# penvmon.net
KiCad netlist of a schematic drawn in EAGLE
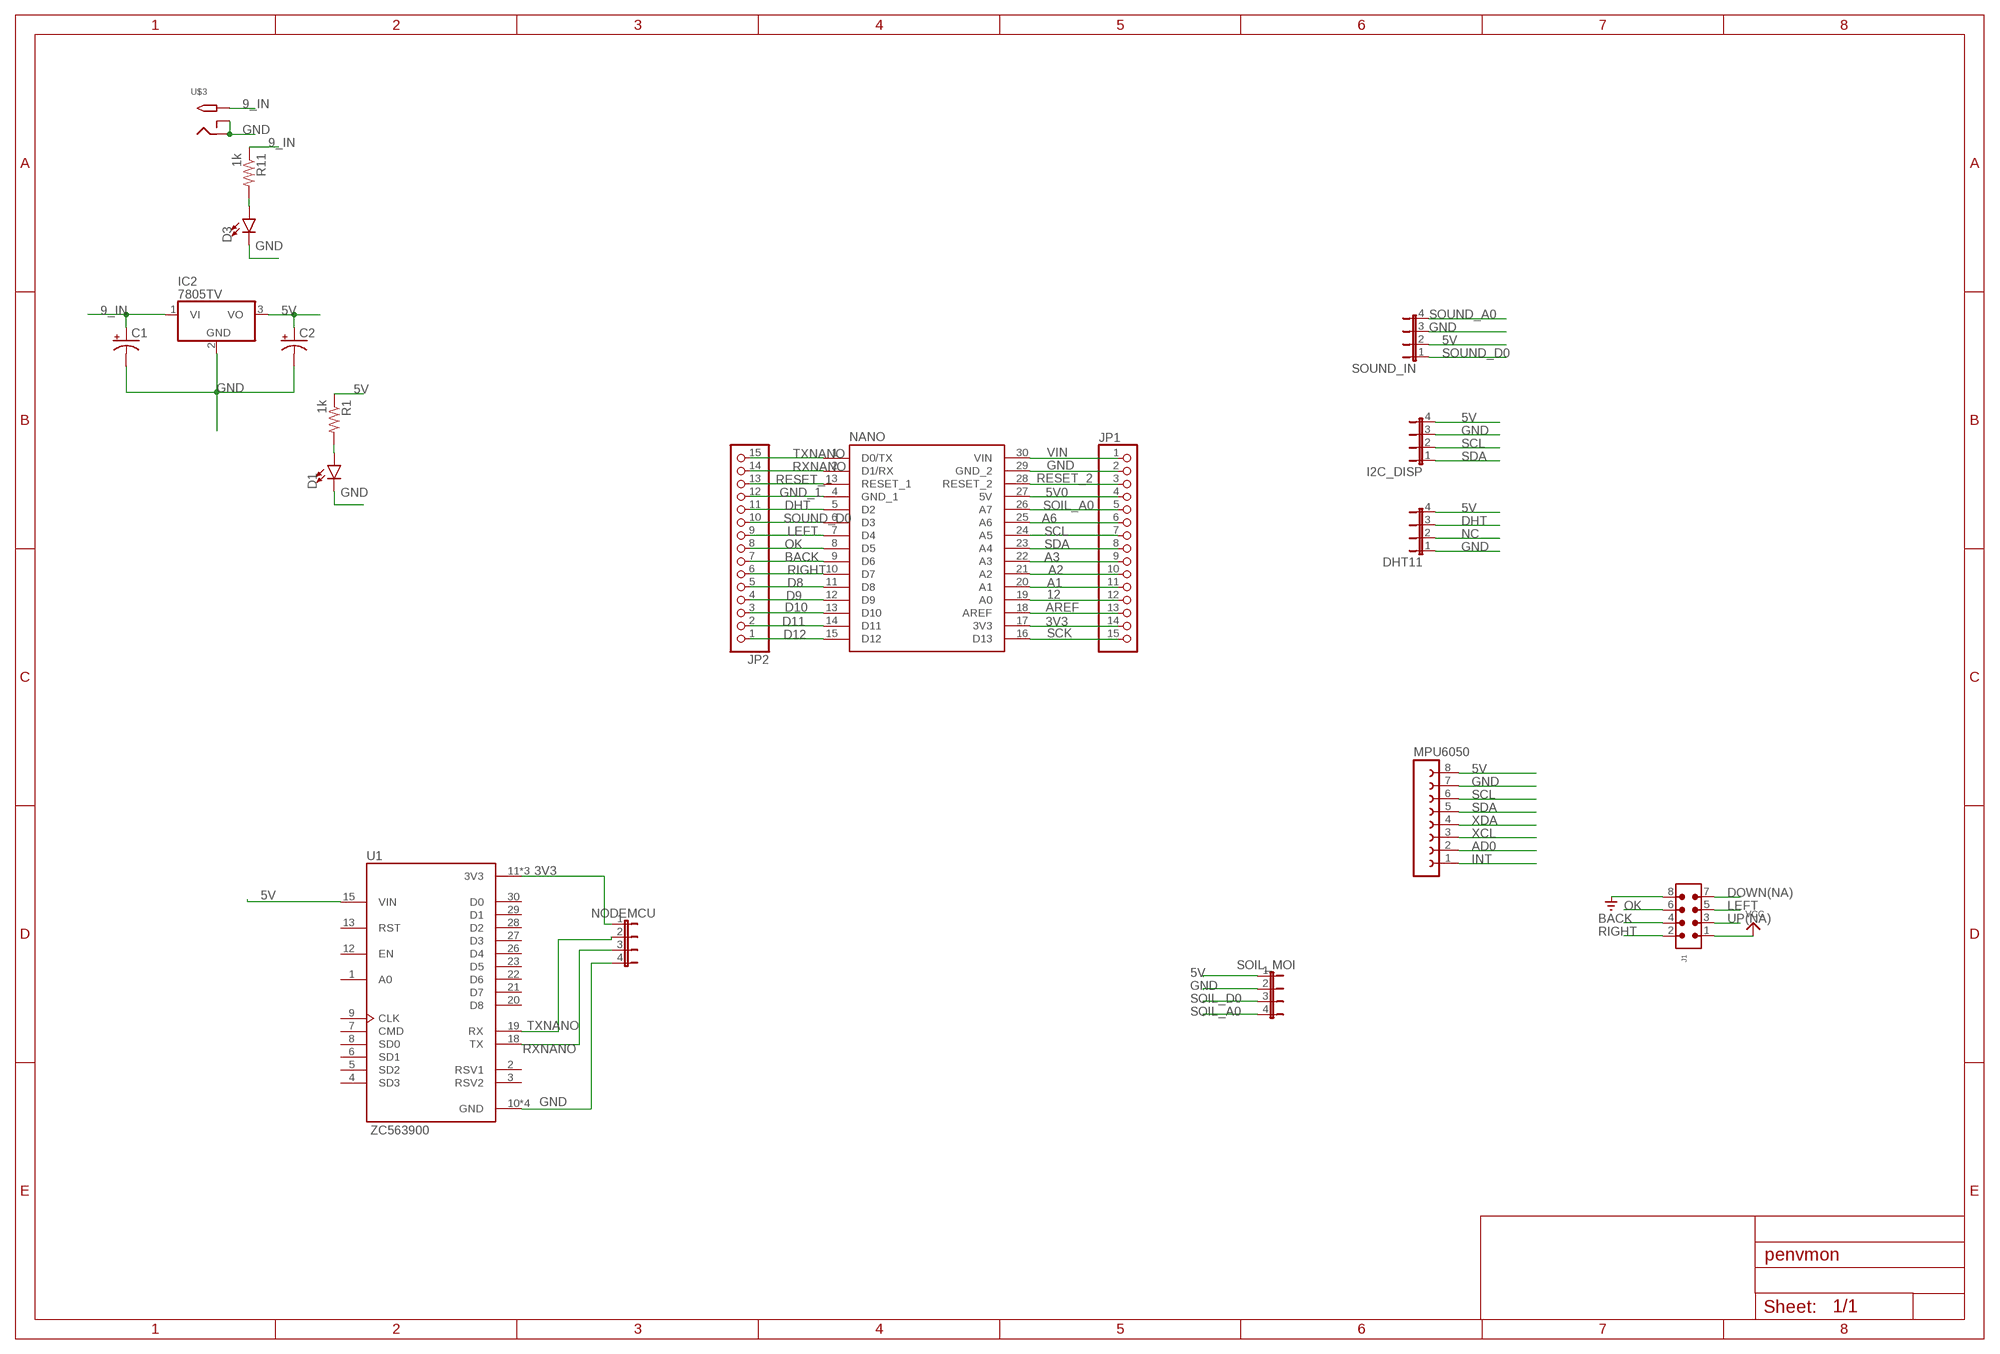
[diagram p0: schematic, sheet 1]

(export (version "E")
  (design (tool "Eeschema 10.0.6"))
  (components
    (comp (ref "C1")
      (value "CPOL-USE3.5-8")
      (footprint "eagle-import:E3,5-8")
      (libsource (lib "eagle-import") (part "CPOL-USE3.5-8"))
    )
    (comp (ref "C2")
      (value "CPOL-USE3.5-8")
      (footprint "eagle-import:E3,5-8")
      (libsource (lib "eagle-import") (part "CPOL-USE3.5-8"))
    )
    (comp (ref "D1")
      (value "LED3MM")
      (footprint "eagle-import:LED_3MM")
      (libsource (lib "eagle-import") (part "LED3MM"))
    )
    (comp (ref "D3")
      (value "LED3MM")
      (footprint "eagle-import:LED_3MM")
      (libsource (lib "eagle-import") (part "LED3MM"))
    )
    (comp (ref "DHT11")
      (value "JP4E")
      (footprint "eagle-import:JP4")
      (libsource (lib "eagle-import") (part "JP4E"))
    )
    (comp (ref "I2C_DISP")
      (value "JP4E")
      (footprint "eagle-import:JP4")
      (libsource (lib "eagle-import") (part "JP4E"))
    )
    (comp (ref "IC2")
      (value "7805TV")
      (footprint "eagle-import:TO220V")
      (libsource (lib "eagle-import") (part "78TV05"))
    )
    (comp (ref "J1")
      (value "6120XX21621_61200821621")
      (footprint "eagle-import:61200821621")
      (libsource (lib "eagle-import") (part "6120XX21621_61200821621"))
    )
    (comp (ref "JP1")
      (value "PINHD-1X15")
      (footprint "eagle-import:1X15")
      (libsource (lib "eagle-import") (part "PINHD-1X15"))
    )
    (comp (ref "JP2")
      (value "PINHD-1X15")
      (footprint "eagle-import:1X15")
      (libsource (lib "eagle-import") (part "PINHD-1X15"))
    )
    (comp (ref "MPU6050")
      (value "FE08-1")
      (footprint "eagle-import:FE08")
      (libsource (lib "eagle-import") (part "FE08-1"))
    )
    (comp (ref "NANO")
      (value "A000005")
      (footprint "eagle-import:MODULE_A000005")
      (fields (field (name "MF") "Arduino"))
      (libsource (lib "eagle-import") (part "A000005"))
    )
    (comp (ref "NODEMCU")
      (value "JP4E")
      (footprint "eagle-import:JP4")
      (libsource (lib "eagle-import") (part "JP4E"))
    )
    (comp (ref "R1")
      (value "1k")
      (footprint "eagle-import:M0805")
      (libsource (lib "eagle-import") (part "R-US_M0805"))
    )
    (comp (ref "R11")
      (value "1k")
      (footprint "eagle-import:M0805")
      (libsource (lib "eagle-import") (part "R-US_M0805"))
    )
    (comp (ref "SOIL_MOI")
      (value "JP4E")
      (footprint "eagle-import:JP4")
      (libsource (lib "eagle-import") (part "JP4E"))
    )
    (comp (ref "SOUND_IN")
      (value "JP4E")
      (footprint "eagle-import:JP4")
      (libsource (lib "eagle-import") (part "JP4E"))
    )
    (comp (ref "U$3")
      (value "2.1MMJACKTHM")
      (footprint "eagle-import:PJ-102A")
      (libsource (lib "eagle-import") (part "2.1MMJACKTHM"))
    )
    (comp (ref "U1")
      (value "ZC563900")
      (footprint "eagle-import:MODULE_ZC563900")
      (fields (field (name "MF") "YKS"))
      (libsource (lib "eagle-import") (part "ZC563900"))
    )
  )
  (nets
    (net (code "1") (name "/3V3") (class "Default")
      (node (ref "JP1") (pin "14") (pinfunction "14_14") (pintype "passive"))
      (node (ref "NANO") (pin "17") (pinfunction "3V3_17") (pintype "power_in"))
      (node (ref "NODEMCU") (pin "1") (pinfunction "1_1") (pintype "passive"))
      (node (ref "U1") (pin "11") (pinfunction "3V3_11") (pintype "power_in"))
      (node (ref "U1") (pin "16") (pinfunction "3V3_16") (pintype "power_in"))
      (node (ref "U1") (pin "25") (pinfunction "3V3_25") (pintype "power_in"))
    )
    (net (code "2") (name "/5V") (class "Default")
      (node (ref "C2") (pin "+") (pinfunction "+_+") (pintype "passive"))
      (node (ref "DHT11") (pin "4") (pinfunction "4_4") (pintype "passive"))
      (node (ref "I2C_DISP") (pin "4") (pinfunction "4_4") (pintype "passive"))
      (node (ref "IC2") (pin "3") (pinfunction "VO_3") (pintype "passive"))
      (node (ref "MPU6050") (pin "8") (pinfunction "8_8") (pintype "passive"))
      (node (ref "R1") (pin "1") (pinfunction "1_1") (pintype "passive"))
      (node (ref "SOIL_MOI") (pin "1") (pinfunction "1_1") (pintype "passive"))
      (node (ref "SOUND_IN") (pin "2") (pinfunction "2_2") (pintype "passive"))
      (node (ref "U1") (pin "15") (pinfunction "VIN_15") (pintype "input"))
    )
    (net (code "3") (name "/5V0") (class "Default")
      (node (ref "JP1") (pin "4") (pinfunction "4_4") (pintype "passive"))
      (node (ref "NANO") (pin "27") (pinfunction "5V_27") (pintype "power_in"))
    )
    (net (code "4") (name "/9_IN") (class "Default")
      (node (ref "C1") (pin "+") (pinfunction "+_+") (pintype "passive"))
      (node (ref "IC2") (pin "1") (pinfunction "VI_1") (pintype "input"))
      (node (ref "R11") (pin "1") (pinfunction "1_1") (pintype "passive"))
      (node (ref "U$3") (pin "TIP") (pinfunction "TIP_TIP") (pintype "bidirectional"))
    )
    (net (code "5") (name "/12") (class "Default")
      (node (ref "JP1") (pin "12") (pinfunction "12_12") (pintype "passive"))
      (node (ref "NANO") (pin "19") (pinfunction "A0_19") (pintype "input"))
    )
    (net (code "6") (name "/A1") (class "Default")
      (node (ref "JP1") (pin "11") (pinfunction "11_11") (pintype "passive"))
      (node (ref "NANO") (pin "20") (pinfunction "A1_20") (pintype "input"))
    )
    (net (code "7") (name "/A2") (class "Default")
      (node (ref "JP1") (pin "10") (pinfunction "10_10") (pintype "passive"))
      (node (ref "NANO") (pin "21") (pinfunction "A2_21") (pintype "input"))
    )
    (net (code "8") (name "/A3") (class "Default")
      (node (ref "JP1") (pin "9") (pinfunction "9_9") (pintype "passive"))
      (node (ref "NANO") (pin "22") (pinfunction "A3_22") (pintype "input"))
    )
    (net (code "9") (name "/A6") (class "Default")
      (node (ref "JP1") (pin "6") (pinfunction "6_6") (pintype "passive"))
      (node (ref "NANO") (pin "25") (pinfunction "A6_25") (pintype "input"))
    )
    (net (code "10") (name "/AD0") (class "Default")
      (node (ref "MPU6050") (pin "2") (pinfunction "2_2") (pintype "passive"))
    )
    (net (code "11") (name "/AREF") (class "Default")
      (node (ref "JP1") (pin "13") (pinfunction "13_13") (pintype "passive"))
      (node (ref "NANO") (pin "18") (pinfunction "AREF_18") (pintype "input"))
    )
    (net (code "12") (name "/BACK") (class "Default")
      (node (ref "J1") (pin "4") (pinfunction "4_4") (pintype "passive"))
      (node (ref "JP2") (pin "7") (pinfunction "7_7") (pintype "passive"))
      (node (ref "NANO") (pin "9") (pinfunction "D6_9") (pintype "bidirectional"))
    )
    (net (code "13") (name "/D8") (class "Default")
      (node (ref "JP2") (pin "5") (pinfunction "5_5") (pintype "passive"))
      (node (ref "NANO") (pin "11") (pinfunction "D8_11") (pintype "bidirectional"))
    )
    (net (code "14") (name "/D9") (class "Default")
      (node (ref "JP2") (pin "4") (pinfunction "4_4") (pintype "passive"))
      (node (ref "NANO") (pin "12") (pinfunction "D9_12") (pintype "bidirectional"))
    )
    (net (code "15") (name "/D10") (class "Default")
      (node (ref "JP2") (pin "3") (pinfunction "3_3") (pintype "passive"))
      (node (ref "NANO") (pin "13") (pinfunction "D10_13") (pintype "bidirectional"))
    )
    (net (code "16") (name "/D11") (class "Default")
      (node (ref "JP2") (pin "2") (pinfunction "2_2") (pintype "passive"))
      (node (ref "NANO") (pin "14") (pinfunction "D11_14") (pintype "bidirectional"))
    )
    (net (code "17") (name "/D12") (class "Default")
      (node (ref "JP2") (pin "1") (pinfunction "1_1") (pintype "passive"))
      (node (ref "NANO") (pin "15") (pinfunction "D12_15") (pintype "bidirectional"))
    )
    (net (code "18") (name "/DHT") (class "Default")
      (node (ref "DHT11") (pin "3") (pinfunction "3_3") (pintype "passive"))
      (node (ref "JP2") (pin "11") (pinfunction "11_11") (pintype "passive"))
      (node (ref "NANO") (pin "5") (pinfunction "D2_5") (pintype "bidirectional"))
    )
    (net (code "19") (name "/DOWN(NA)") (class "Default")
      (node (ref "J1") (pin "7") (pinfunction "7_7") (pintype "passive"))
    )
    (net (code "20") (name "/GND_1") (class "Default")
      (node (ref "JP2") (pin "12") (pinfunction "12_12") (pintype "passive"))
      (node (ref "NANO") (pin "4") (pinfunction "GND_1_4") (pintype "power_in"))
    )
    (net (code "21") (name "/INT") (class "Default")
      (node (ref "MPU6050") (pin "1") (pinfunction "1_1") (pintype "passive"))
    )
    (net (code "22") (name "/LEFT") (class "Default")
      (node (ref "J1") (pin "5") (pinfunction "5_5") (pintype "passive"))
      (node (ref "JP2") (pin "9") (pinfunction "9_9") (pintype "passive"))
      (node (ref "NANO") (pin "7") (pinfunction "D4_7") (pintype "bidirectional"))
    )
    (net (code "23") (name "/NC") (class "Default")
      (node (ref "DHT11") (pin "2") (pinfunction "2_2") (pintype "passive"))
    )
    (net (code "24") (name "/OK") (class "Default")
      (node (ref "J1") (pin "6") (pinfunction "6_6") (pintype "passive"))
      (node (ref "JP2") (pin "8") (pinfunction "8_8") (pintype "passive"))
      (node (ref "NANO") (pin "8") (pinfunction "D5_8") (pintype "bidirectional"))
    )
    (net (code "25") (name "/RESET_1") (class "Default")
      (node (ref "JP2") (pin "13") (pinfunction "13_13") (pintype "passive"))
      (node (ref "NANO") (pin "3") (pinfunction "RESET_1_3") (pintype "input"))
    )
    (net (code "26") (name "/RESET_2") (class "Default")
      (node (ref "JP1") (pin "3") (pinfunction "3_3") (pintype "passive"))
      (node (ref "NANO") (pin "28") (pinfunction "RESET_2_28") (pintype "input"))
    )
    (net (code "27") (name "/RIGHT") (class "Default")
      (node (ref "J1") (pin "2") (pinfunction "2_2") (pintype "passive"))
      (node (ref "JP2") (pin "6") (pinfunction "6_6") (pintype "passive"))
      (node (ref "NANO") (pin "10") (pinfunction "D7_10") (pintype "bidirectional"))
    )
    (net (code "28") (name "/RXNANO") (class "Default")
      (node (ref "JP2") (pin "14") (pinfunction "14_14") (pintype "passive"))
      (node (ref "NANO") (pin "2") (pinfunction "D1/RX_2") (pintype "bidirectional"))
      (node (ref "NODEMCU") (pin "3") (pinfunction "3_3") (pintype "passive"))
      (node (ref "U1") (pin "18") (pinfunction "TX_18") (pintype "bidirectional"))
    )
    (net (code "29") (name "/SCK") (class "Default")
      (node (ref "JP1") (pin "15") (pinfunction "15_15") (pintype "passive"))
      (node (ref "NANO") (pin "16") (pinfunction "D13_16") (pintype "bidirectional"))
    )
    (net (code "30") (name "/SCL") (class "Default")
      (node (ref "I2C_DISP") (pin "2") (pinfunction "2_2") (pintype "passive"))
      (node (ref "JP1") (pin "7") (pinfunction "7_7") (pintype "passive"))
      (node (ref "MPU6050") (pin "6") (pinfunction "6_6") (pintype "passive"))
      (node (ref "NANO") (pin "24") (pinfunction "A5_24") (pintype "input"))
    )
    (net (code "31") (name "/SDA") (class "Default")
      (node (ref "I2C_DISP") (pin "1") (pinfunction "1_1") (pintype "passive"))
      (node (ref "JP1") (pin "8") (pinfunction "8_8") (pintype "passive"))
      (node (ref "MPU6050") (pin "5") (pinfunction "5_5") (pintype "passive"))
      (node (ref "NANO") (pin "23") (pinfunction "A4_23") (pintype "input"))
    )
    (net (code "32") (name "/SOIL_A0") (class "Default")
      (node (ref "JP1") (pin "5") (pinfunction "5_5") (pintype "passive"))
      (node (ref "NANO") (pin "26") (pinfunction "A7_26") (pintype "input"))
      (node (ref "SOIL_MOI") (pin "4") (pinfunction "4_4") (pintype "passive"))
    )
    (net (code "33") (name "/SOIL_D0") (class "Default")
      (node (ref "SOIL_MOI") (pin "3") (pinfunction "3_3") (pintype "passive"))
    )
    (net (code "34") (name "/SOUND_A0") (class "Default")
      (node (ref "SOUND_IN") (pin "4") (pinfunction "4_4") (pintype "passive"))
    )
    (net (code "35") (name "/SOUND_D0") (class "Default")
      (node (ref "JP2") (pin "10") (pinfunction "10_10") (pintype "passive"))
      (node (ref "NANO") (pin "6") (pinfunction "D3_6") (pintype "bidirectional"))
      (node (ref "SOUND_IN") (pin "1") (pinfunction "1_1") (pintype "passive"))
    )
    (net (code "36") (name "/TXNANO") (class "Default")
      (node (ref "JP2") (pin "15") (pinfunction "15_15") (pintype "passive"))
      (node (ref "NANO") (pin "1") (pinfunction "D0/TX_1") (pintype "bidirectional"))
      (node (ref "NODEMCU") (pin "2") (pinfunction "2_2") (pintype "passive"))
      (node (ref "U1") (pin "19") (pinfunction "RX_19") (pintype "bidirectional"))
    )
    (net (code "37") (name "/UP(NA)") (class "Default")
      (node (ref "J1") (pin "3") (pinfunction "3_3") (pintype "passive"))
    )
    (net (code "38") (name "/VIN") (class "Default")
      (node (ref "JP1") (pin "1") (pinfunction "1_1") (pintype "passive"))
      (node (ref "NANO") (pin "30") (pinfunction "VIN_30") (pintype "power_in"))
    )
    (net (code "39") (name "/XCL") (class "Default")
      (node (ref "MPU6050") (pin "3") (pinfunction "3_3") (pintype "passive"))
    )
    (net (code "40") (name "/XDA") (class "Default")
      (node (ref "MPU6050") (pin "4") (pinfunction "4_4") (pintype "passive"))
    )
    (net (code "41") (name "Net-(D1-PadA)") (class "Default")
      (node (ref "D1") (pin "A") (pinfunction "A_A") (pintype "passive"))
      (node (ref "R1") (pin "2") (pinfunction "2_2") (pintype "passive"))
    )
    (net (code "42") (name "Net-(D3-PadA)") (class "Default")
      (node (ref "D3") (pin "A") (pinfunction "A_A") (pintype "passive"))
      (node (ref "R11") (pin "2") (pinfunction "2_2") (pintype "passive"))
    )
    (net (code "43") (name "SUPPLY0_GND_") (class "Default")
      (node (ref "C1") (pin "-") (pinfunction "-_-") (pintype "passive"))
      (node (ref "C2") (pin "-") (pinfunction "-_-") (pintype "passive"))
      (node (ref "D1") (pin "K") (pinfunction "C_K") (pintype "passive"))
      (node (ref "D3") (pin "K") (pinfunction "C_K") (pintype "passive"))
      (node (ref "DHT11") (pin "1") (pinfunction "1_1") (pintype "passive"))
      (node (ref "I2C_DISP") (pin "3") (pinfunction "3_3") (pintype "passive"))
      (node (ref "IC2") (pin "2") (pinfunction "GND_2") (pintype "passive"))
      (node (ref "J1") (pin "8") (pinfunction "8_8") (pintype "passive"))
      (node (ref "JP1") (pin "2") (pinfunction "2_2") (pintype "passive"))
      (node (ref "MPU6050") (pin "7") (pinfunction "7_7") (pintype "passive"))
      (node (ref "NANO") (pin "29") (pinfunction "GND_2_29") (pintype "power_in"))
      (node (ref "NODEMCU") (pin "4") (pinfunction "4_4") (pintype "passive"))
      (node (ref "SOIL_MOI") (pin "2") (pinfunction "2_2") (pintype "passive"))
      (node (ref "SOUND_IN") (pin "3") (pinfunction "3_3") (pintype "passive"))
      (node (ref "U$3") (pin "RING") (pinfunction "RING_RING") (pintype "bidirectional"))
      (node (ref "U$3") (pin "RING_SW") (pinfunction "RING_SW_RING_SW") (pintype "bidirectional"))
      (node (ref "U1") (pin "10") (pinfunction "GND_10") (pintype "power_in"))
      (node (ref "U1") (pin "14") (pinfunction "GND_14") (pintype "power_in"))
      (node (ref "U1") (pin "17") (pinfunction "GND_17") (pintype "power_in"))
      (node (ref "U1") (pin "24") (pinfunction "GND_24") (pintype "power_in"))
    )
    (net (code "44") (name "VCC") (class "Default")
      (node (ref "J1") (pin "1") (pinfunction "1_1") (pintype "passive"))
    )
    (net (code "45") (name "unconnected-(U1-A0-Pad1)") (class "Default")
      (node (ref "U1") (pin "1") (pinfunction "A0_1") (pintype "input"))
    )
    (net (code "46") (name "unconnected-(U1-CLK-Pad9)") (class "Default")
      (node (ref "U1") (pin "9") (pinfunction "CLK_9") (pintype "input"))
    )
    (net (code "47") (name "unconnected-(U1-CMD-Pad7)") (class "Default")
      (node (ref "U1") (pin "7") (pinfunction "CMD_7") (pintype "input"))
    )
    (net (code "48") (name "unconnected-(U1-D0-Pad30)") (class "Default")
      (node (ref "U1") (pin "30") (pinfunction "D0_30") (pintype "bidirectional"))
    )
    (net (code "49") (name "unconnected-(U1-D1-Pad29)") (class "Default")
      (node (ref "U1") (pin "29") (pinfunction "D1_29") (pintype "bidirectional"))
    )
    (net (code "50") (name "unconnected-(U1-D2-Pad28)") (class "Default")
      (node (ref "U1") (pin "28") (pinfunction "D2_28") (pintype "bidirectional"))
    )
    (net (code "51") (name "unconnected-(U1-D3-Pad27)") (class "Default")
      (node (ref "U1") (pin "27") (pinfunction "D3_27") (pintype "bidirectional"))
    )
    (net (code "52") (name "unconnected-(U1-D4-Pad26)") (class "Default")
      (node (ref "U1") (pin "26") (pinfunction "D4_26") (pintype "bidirectional"))
    )
    (net (code "53") (name "unconnected-(U1-D5-Pad23)") (class "Default")
      (node (ref "U1") (pin "23") (pinfunction "D5_23") (pintype "bidirectional"))
    )
    (net (code "54") (name "unconnected-(U1-D6-Pad22)") (class "Default")
      (node (ref "U1") (pin "22") (pinfunction "D6_22") (pintype "bidirectional"))
    )
    (net (code "55") (name "unconnected-(U1-D7-Pad21)") (class "Default")
      (node (ref "U1") (pin "21") (pinfunction "D7_21") (pintype "bidirectional"))
    )
    (net (code "56") (name "unconnected-(U1-D8-Pad20)") (class "Default")
      (node (ref "U1") (pin "20") (pinfunction "D8_20") (pintype "bidirectional"))
    )
    (net (code "57") (name "unconnected-(U1-EN-Pad12)") (class "Default")
      (node (ref "U1") (pin "12") (pinfunction "EN_12") (pintype "input"))
    )
    (net (code "58") (name "unconnected-(U1-RST-Pad13)") (class "Default")
      (node (ref "U1") (pin "13") (pinfunction "RST_13") (pintype "input"))
    )
    (net (code "59") (name "unconnected-(U1-RSV1-Pad2)") (class "Default")
      (node (ref "U1") (pin "2") (pinfunction "RSV1_2") (pintype "passive"))
    )
    (net (code "60") (name "unconnected-(U1-RSV2-Pad3)") (class "Default")
      (node (ref "U1") (pin "3") (pinfunction "RSV2_3") (pintype "passive"))
    )
    (net (code "61") (name "unconnected-(U1-SD0-Pad8)") (class "Default")
      (node (ref "U1") (pin "8") (pinfunction "SD0_8") (pintype "bidirectional"))
    )
    (net (code "62") (name "unconnected-(U1-SD1-Pad6)") (class "Default")
      (node (ref "U1") (pin "6") (pinfunction "SD1_6") (pintype "bidirectional"))
    )
    (net (code "63") (name "unconnected-(U1-SD2-Pad5)") (class "Default")
      (node (ref "U1") (pin "5") (pinfunction "SD2_5") (pintype "bidirectional"))
    )
    (net (code "64") (name "unconnected-(U1-SD3-Pad4)") (class "Default")
      (node (ref "U1") (pin "4") (pinfunction "SD3_4") (pintype "bidirectional"))
    )
  )
)
